# IO4-SignalDriver.net
KiCad netlist of a schematic drawn in EAGLE
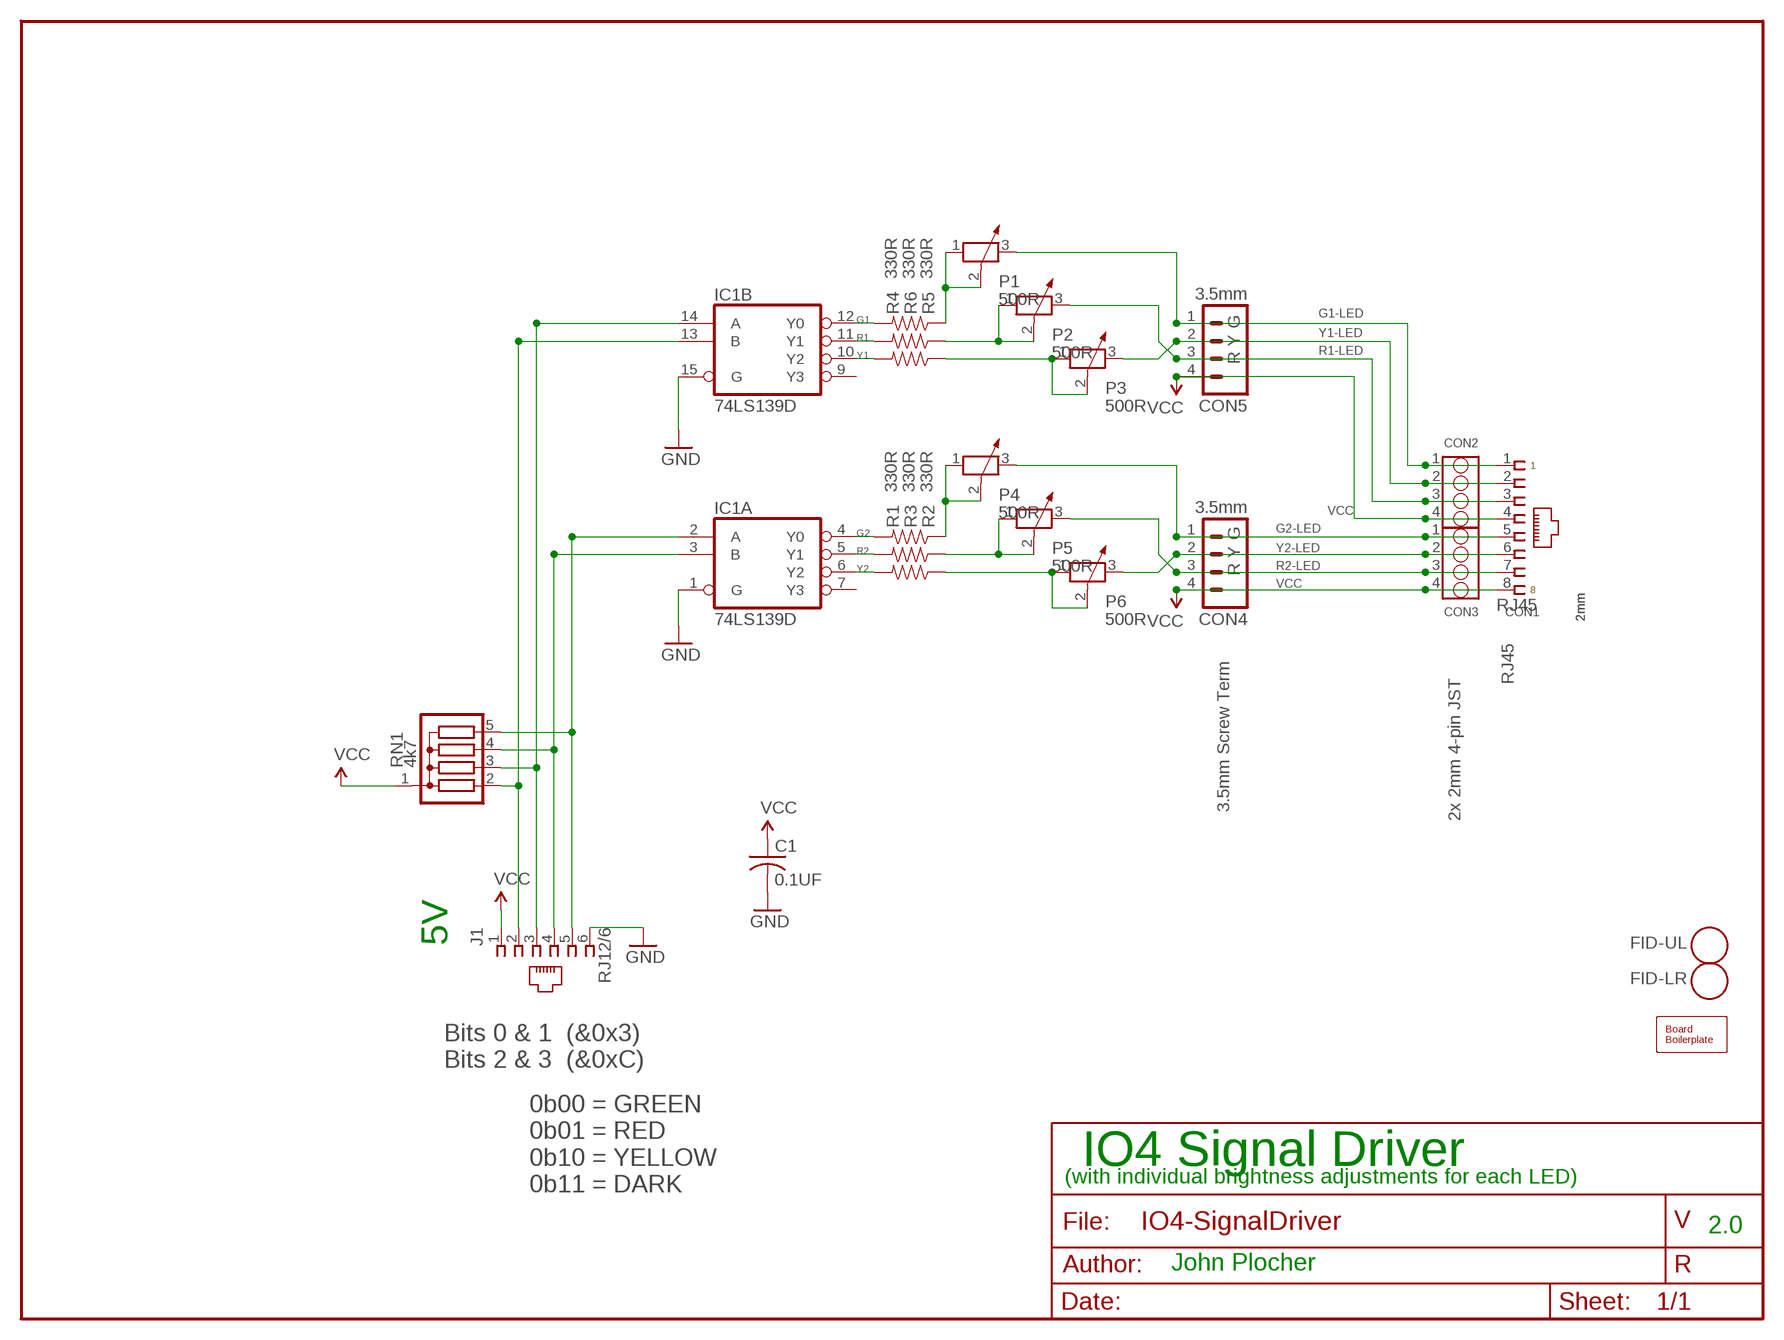
[diagram p0: schematic, sheet 1]

(export (version "E")
  (design (tool "Eeschema 10.0.6"))
  (components
    (comp (ref "BOARD1")
      (value "BOARD")
      (footprint "eagle-import:BOARD-DINRAIL-3.17INX10CM")
      (libsource (lib "eagle-import") (part "BOARD80X100"))
    )
    (comp (ref "C1")
      (value "0.1UF")
      (footprint "eagle-import:0603-CAP")
      (libsource (lib "eagle-import") (part "CAP0603"))
    )
    (comp (ref "CON1")
      (value "RJ45")
      (footprint "eagle-import:RJ45-NO-SHIELD")
      (libsource (lib "eagle-import") (part "CONNECTOR-RJ45-FRONT"))
    )
    (comp (ref "CON2")
      (value "2mm")
      (footprint "eagle-import:4P-2.0")
      (libsource (lib "eagle-import") (part "CONNECTOR-GROVE-4P-2.0-3470130P1"))
    )
    (comp (ref "CON3")
      (value "2mm")
      (footprint "eagle-import:4P-2.0")
      (libsource (lib "eagle-import") (part "CONNECTOR-GROVE-4P-2.0-3470130P1"))
    )
    (comp (ref "CON4")
      (value "3.5mm")
      (footprint "eagle-import:SCREWTERMINAL-3.5MM-4_LOCK")
      (libsource (lib "eagle-import") (part "M04SCREW_LOCK"))
    )
    (comp (ref "CON5")
      (value "3.5mm")
      (footprint "eagle-import:SCREWTERMINAL-3.5MM-4_LOCK")
      (libsource (lib "eagle-import") (part "M04SCREW_LOCK"))
    )
    (comp (ref "FID-LR")
      (value "FIDUCIAL")
      (footprint "eagle-import:FIDUCIAL_1MM")
      (libsource (lib "eagle-import") (part "FIDUCIAL"))
    )
    (comp (ref "FID-UL")
      (value "FIDUCIAL")
      (footprint "eagle-import:FIDUCIAL_1MM")
      (libsource (lib "eagle-import") (part "FIDUCIAL"))
    )
    (comp (ref "IC1")
      (value "74LS139D")
      (footprint "eagle-import:SO16")
      (libsource (lib "eagle-import") (part "74139DLS"))
    )
    (comp (ref "J1")
      (value "RJ12/6")
      (footprint "eagle-import:RJ25-PANEL")
      (libsource (lib "eagle-import") (part "CONNECTOR-RJ25-6P6C"))
    )
    (comp (ref "P1")
      (value "500R")
      (footprint "eagle-import:P-3319")
      (libsource (lib "eagle-import") (part "R-POTENTIOMETERP-3319"))
    )
    (comp (ref "P2")
      (value "500R")
      (footprint "eagle-import:P-3319")
      (libsource (lib "eagle-import") (part "R-POTENTIOMETERP-3319"))
    )
    (comp (ref "P3")
      (value "500R")
      (footprint "eagle-import:P-3319")
      (libsource (lib "eagle-import") (part "R-POTENTIOMETERP-3319"))
    )
    (comp (ref "P4")
      (value "500R")
      (footprint "eagle-import:P-3319")
      (libsource (lib "eagle-import") (part "R-POTENTIOMETERP-3319"))
    )
    (comp (ref "P5")
      (value "500R")
      (footprint "eagle-import:P-3319")
      (libsource (lib "eagle-import") (part "R-POTENTIOMETERP-3319"))
    )
    (comp (ref "P6")
      (value "500R")
      (footprint "eagle-import:P-3319")
      (libsource (lib "eagle-import") (part "R-POTENTIOMETERP-3319"))
    )
    (comp (ref "R1")
      (value "330R")
      (footprint "eagle-import:0805-RES")
      (libsource (lib "eagle-import") (part "R0805-RES"))
    )
    (comp (ref "R2")
      (value "330R")
      (footprint "eagle-import:0805-RES")
      (libsource (lib "eagle-import") (part "R0805-RES"))
    )
    (comp (ref "R3")
      (value "330R")
      (footprint "eagle-import:0805-RES")
      (libsource (lib "eagle-import") (part "R0805-RES"))
    )
    (comp (ref "R4")
      (value "330R")
      (footprint "eagle-import:0805-RES")
      (libsource (lib "eagle-import") (part "R0805-RES"))
    )
    (comp (ref "R5")
      (value "330R")
      (footprint "eagle-import:0805-RES")
      (libsource (lib "eagle-import") (part "R0805-RES"))
    )
    (comp (ref "R6")
      (value "330R")
      (footprint "eagle-import:0805-RES")
      (libsource (lib "eagle-import") (part "R0805-RES"))
    )
    (comp (ref "RN1")
      (value "4k7")
      (footprint "eagle-import:SIL5")
      (libsource (lib "eagle-import") (part "G04R"))
    )
  )
  (nets
    (net (code "1") (name "/G1") (class "Default")
      (node (ref "IC1") (pin "12") (pinfunction "Y0_12") (pintype "output"))
      (node (ref "R4") (pin "2") (pinfunction "2_2") (pintype "passive"))
    )
    (net (code "2") (name "/G1-LED") (class "Default")
      (node (ref "CON1") (pin "1") (pinfunction "1_1") (pintype "passive"))
      (node (ref "CON2") (pin "1") (pinfunction "1_1") (pintype "bidirectional"))
      (node (ref "CON5") (pin "1") (pinfunction "1_1") (pintype "passive"))
      (node (ref "P1") (pin "3") (pinfunction "3_3") (pintype "passive"))
    )
    (net (code "3") (name "/G2") (class "Default")
      (node (ref "IC1") (pin "4") (pinfunction "Y0_4") (pintype "output"))
      (node (ref "R1") (pin "2") (pinfunction "2_2") (pintype "passive"))
    )
    (net (code "4") (name "/G2-LED") (class "Default")
      (node (ref "CON1") (pin "5") (pinfunction "5_5") (pintype "passive"))
      (node (ref "CON3") (pin "1") (pinfunction "1_1") (pintype "bidirectional"))
      (node (ref "CON4") (pin "1") (pinfunction "1_1") (pintype "passive"))
      (node (ref "P4") (pin "3") (pinfunction "3_3") (pintype "passive"))
    )
    (net (code "5") (name "/R1") (class "Default")
      (node (ref "IC1") (pin "11") (pinfunction "Y1_11") (pintype "output"))
      (node (ref "R6") (pin "2") (pinfunction "2_2") (pintype "passive"))
    )
    (net (code "6") (name "/R1-LED") (class "Default")
      (node (ref "CON1") (pin "3") (pinfunction "3_3") (pintype "passive"))
      (node (ref "CON2") (pin "3") (pinfunction "3_3") (pintype "bidirectional"))
      (node (ref "CON5") (pin "3") (pinfunction "3_3") (pintype "passive"))
      (node (ref "P2") (pin "3") (pinfunction "3_3") (pintype "passive"))
    )
    (net (code "7") (name "/R2") (class "Default")
      (node (ref "IC1") (pin "5") (pinfunction "Y1_5") (pintype "output"))
      (node (ref "R3") (pin "2") (pinfunction "2_2") (pintype "passive"))
    )
    (net (code "8") (name "/R2-LED") (class "Default")
      (node (ref "CON1") (pin "7") (pinfunction "7_7") (pintype "passive"))
      (node (ref "CON3") (pin "3") (pinfunction "3_3") (pintype "bidirectional"))
      (node (ref "CON4") (pin "3") (pinfunction "3_3") (pintype "passive"))
      (node (ref "P5") (pin "3") (pinfunction "3_3") (pintype "passive"))
    )
    (net (code "9") (name "/Y1") (class "Default")
      (node (ref "IC1") (pin "10") (pinfunction "Y2_10") (pintype "output"))
      (node (ref "R5") (pin "2") (pinfunction "2_2") (pintype "passive"))
    )
    (net (code "10") (name "/Y1-LED") (class "Default")
      (node (ref "CON1") (pin "2") (pinfunction "2_2") (pintype "passive"))
      (node (ref "CON2") (pin "2") (pinfunction "2_2") (pintype "bidirectional"))
      (node (ref "CON5") (pin "2") (pinfunction "2_2") (pintype "passive"))
      (node (ref "P3") (pin "3") (pinfunction "3_3") (pintype "passive"))
    )
    (net (code "11") (name "/Y2") (class "Default")
      (node (ref "IC1") (pin "6") (pinfunction "Y2_6") (pintype "output"))
      (node (ref "R2") (pin "2") (pinfunction "2_2") (pintype "passive"))
    )
    (net (code "12") (name "/Y2-LED") (class "Default")
      (node (ref "CON1") (pin "6") (pinfunction "6_6") (pintype "passive"))
      (node (ref "CON3") (pin "2") (pinfunction "2_2") (pintype "bidirectional"))
      (node (ref "CON4") (pin "2") (pinfunction "2_2") (pintype "passive"))
      (node (ref "P6") (pin "3") (pinfunction "3_3") (pintype "passive"))
    )
    (net (code "13") (name "GND") (class "Default")
      (node (ref "C1") (pin "2") (pinfunction "2_2") (pintype "passive"))
      (node (ref "IC1") (pin "1") (pinfunction "G_1") (pintype "input"))
      (node (ref "IC1") (pin "15") (pinfunction "G_15") (pintype "input"))
      (node (ref "J1") (pin "6") (pinfunction "6_6") (pintype "passive"))
    )
    (net (code "14") (name "Net-(IC1A-A)") (class "Default")
      (node (ref "IC1") (pin "2") (pinfunction "A_2") (pintype "input"))
      (node (ref "J1") (pin "5") (pinfunction "5_5") (pintype "passive"))
      (node (ref "RN1") (pin "5") (pinfunction "5_5") (pintype "passive"))
    )
    (net (code "15") (name "Net-(IC1A-B)") (class "Default")
      (node (ref "IC1") (pin "3") (pinfunction "B_3") (pintype "input"))
      (node (ref "J1") (pin "4") (pinfunction "4_4") (pintype "passive"))
      (node (ref "RN1") (pin "4") (pinfunction "4_4") (pintype "passive"))
    )
    (net (code "16") (name "Net-(IC1B-A)") (class "Default")
      (node (ref "IC1") (pin "14") (pinfunction "A_14") (pintype "input"))
      (node (ref "J1") (pin "3") (pinfunction "3_3") (pintype "passive"))
      (node (ref "RN1") (pin "3") (pinfunction "3_3") (pintype "passive"))
    )
    (net (code "17") (name "Net-(IC1B-B)") (class "Default")
      (node (ref "IC1") (pin "13") (pinfunction "B_13") (pintype "input"))
      (node (ref "J1") (pin "2") (pinfunction "2_2") (pintype "passive"))
      (node (ref "RN1") (pin "2") (pinfunction "2_2") (pintype "passive"))
    )
    (net (code "18") (name "Net-(P1-Pad1)") (class "Default")
      (node (ref "P1") (pin "1") (pinfunction "1_1") (pintype "passive"))
      (node (ref "P1") (pin "2") (pinfunction "2_2") (pintype "passive"))
      (node (ref "R4") (pin "1") (pinfunction "1_1") (pintype "passive"))
    )
    (net (code "19") (name "Net-(P2-Pad1)") (class "Default")
      (node (ref "P2") (pin "1") (pinfunction "1_1") (pintype "passive"))
      (node (ref "P2") (pin "2") (pinfunction "2_2") (pintype "passive"))
      (node (ref "R6") (pin "1") (pinfunction "1_1") (pintype "passive"))
    )
    (net (code "20") (name "Net-(P3-Pad1)") (class "Default")
      (node (ref "P3") (pin "1") (pinfunction "1_1") (pintype "passive"))
      (node (ref "P3") (pin "2") (pinfunction "2_2") (pintype "passive"))
      (node (ref "R5") (pin "1") (pinfunction "1_1") (pintype "passive"))
    )
    (net (code "21") (name "Net-(P4-Pad1)") (class "Default")
      (node (ref "P4") (pin "1") (pinfunction "1_1") (pintype "passive"))
      (node (ref "P4") (pin "2") (pinfunction "2_2") (pintype "passive"))
      (node (ref "R1") (pin "1") (pinfunction "1_1") (pintype "passive"))
    )
    (net (code "22") (name "Net-(P5-Pad1)") (class "Default")
      (node (ref "P5") (pin "1") (pinfunction "1_1") (pintype "passive"))
      (node (ref "P5") (pin "2") (pinfunction "2_2") (pintype "passive"))
      (node (ref "R3") (pin "1") (pinfunction "1_1") (pintype "passive"))
    )
    (net (code "23") (name "Net-(P6-Pad1)") (class "Default")
      (node (ref "P6") (pin "1") (pinfunction "1_1") (pintype "passive"))
      (node (ref "P6") (pin "2") (pinfunction "2_2") (pintype "passive"))
      (node (ref "R2") (pin "1") (pinfunction "1_1") (pintype "passive"))
    )
    (net (code "24") (name "VCC") (class "Default")
      (node (ref "C1") (pin "1") (pinfunction "1_1") (pintype "passive"))
      (node (ref "CON1") (pin "4") (pinfunction "4_4") (pintype "passive"))
      (node (ref "CON1") (pin "8") (pinfunction "8_8") (pintype "passive"))
      (node (ref "CON2") (pin "4") (pinfunction "4_4") (pintype "bidirectional"))
      (node (ref "CON3") (pin "4") (pinfunction "4_4") (pintype "bidirectional"))
      (node (ref "CON4") (pin "4") (pinfunction "4_4") (pintype "passive"))
      (node (ref "CON5") (pin "4") (pinfunction "4_4") (pintype "passive"))
      (node (ref "J1") (pin "1") (pinfunction "1_1") (pintype "passive"))
      (node (ref "RN1") (pin "1") (pinfunction "1_1") (pintype "passive"))
    )
    (net (code "25") (name "unconnected-(IC1A-Y3-Pad7)") (class "Default")
      (node (ref "IC1") (pin "7") (pinfunction "Y3_7") (pintype "output"))
    )
    (net (code "26") (name "unconnected-(IC1B-Y3-Pad9)") (class "Default")
      (node (ref "IC1") (pin "9") (pinfunction "Y3_9") (pintype "output"))
    )
  )
)
